# LeoBlinky2018-ENT.net
KiCad netlist of a schematic drawn in Altium Designer
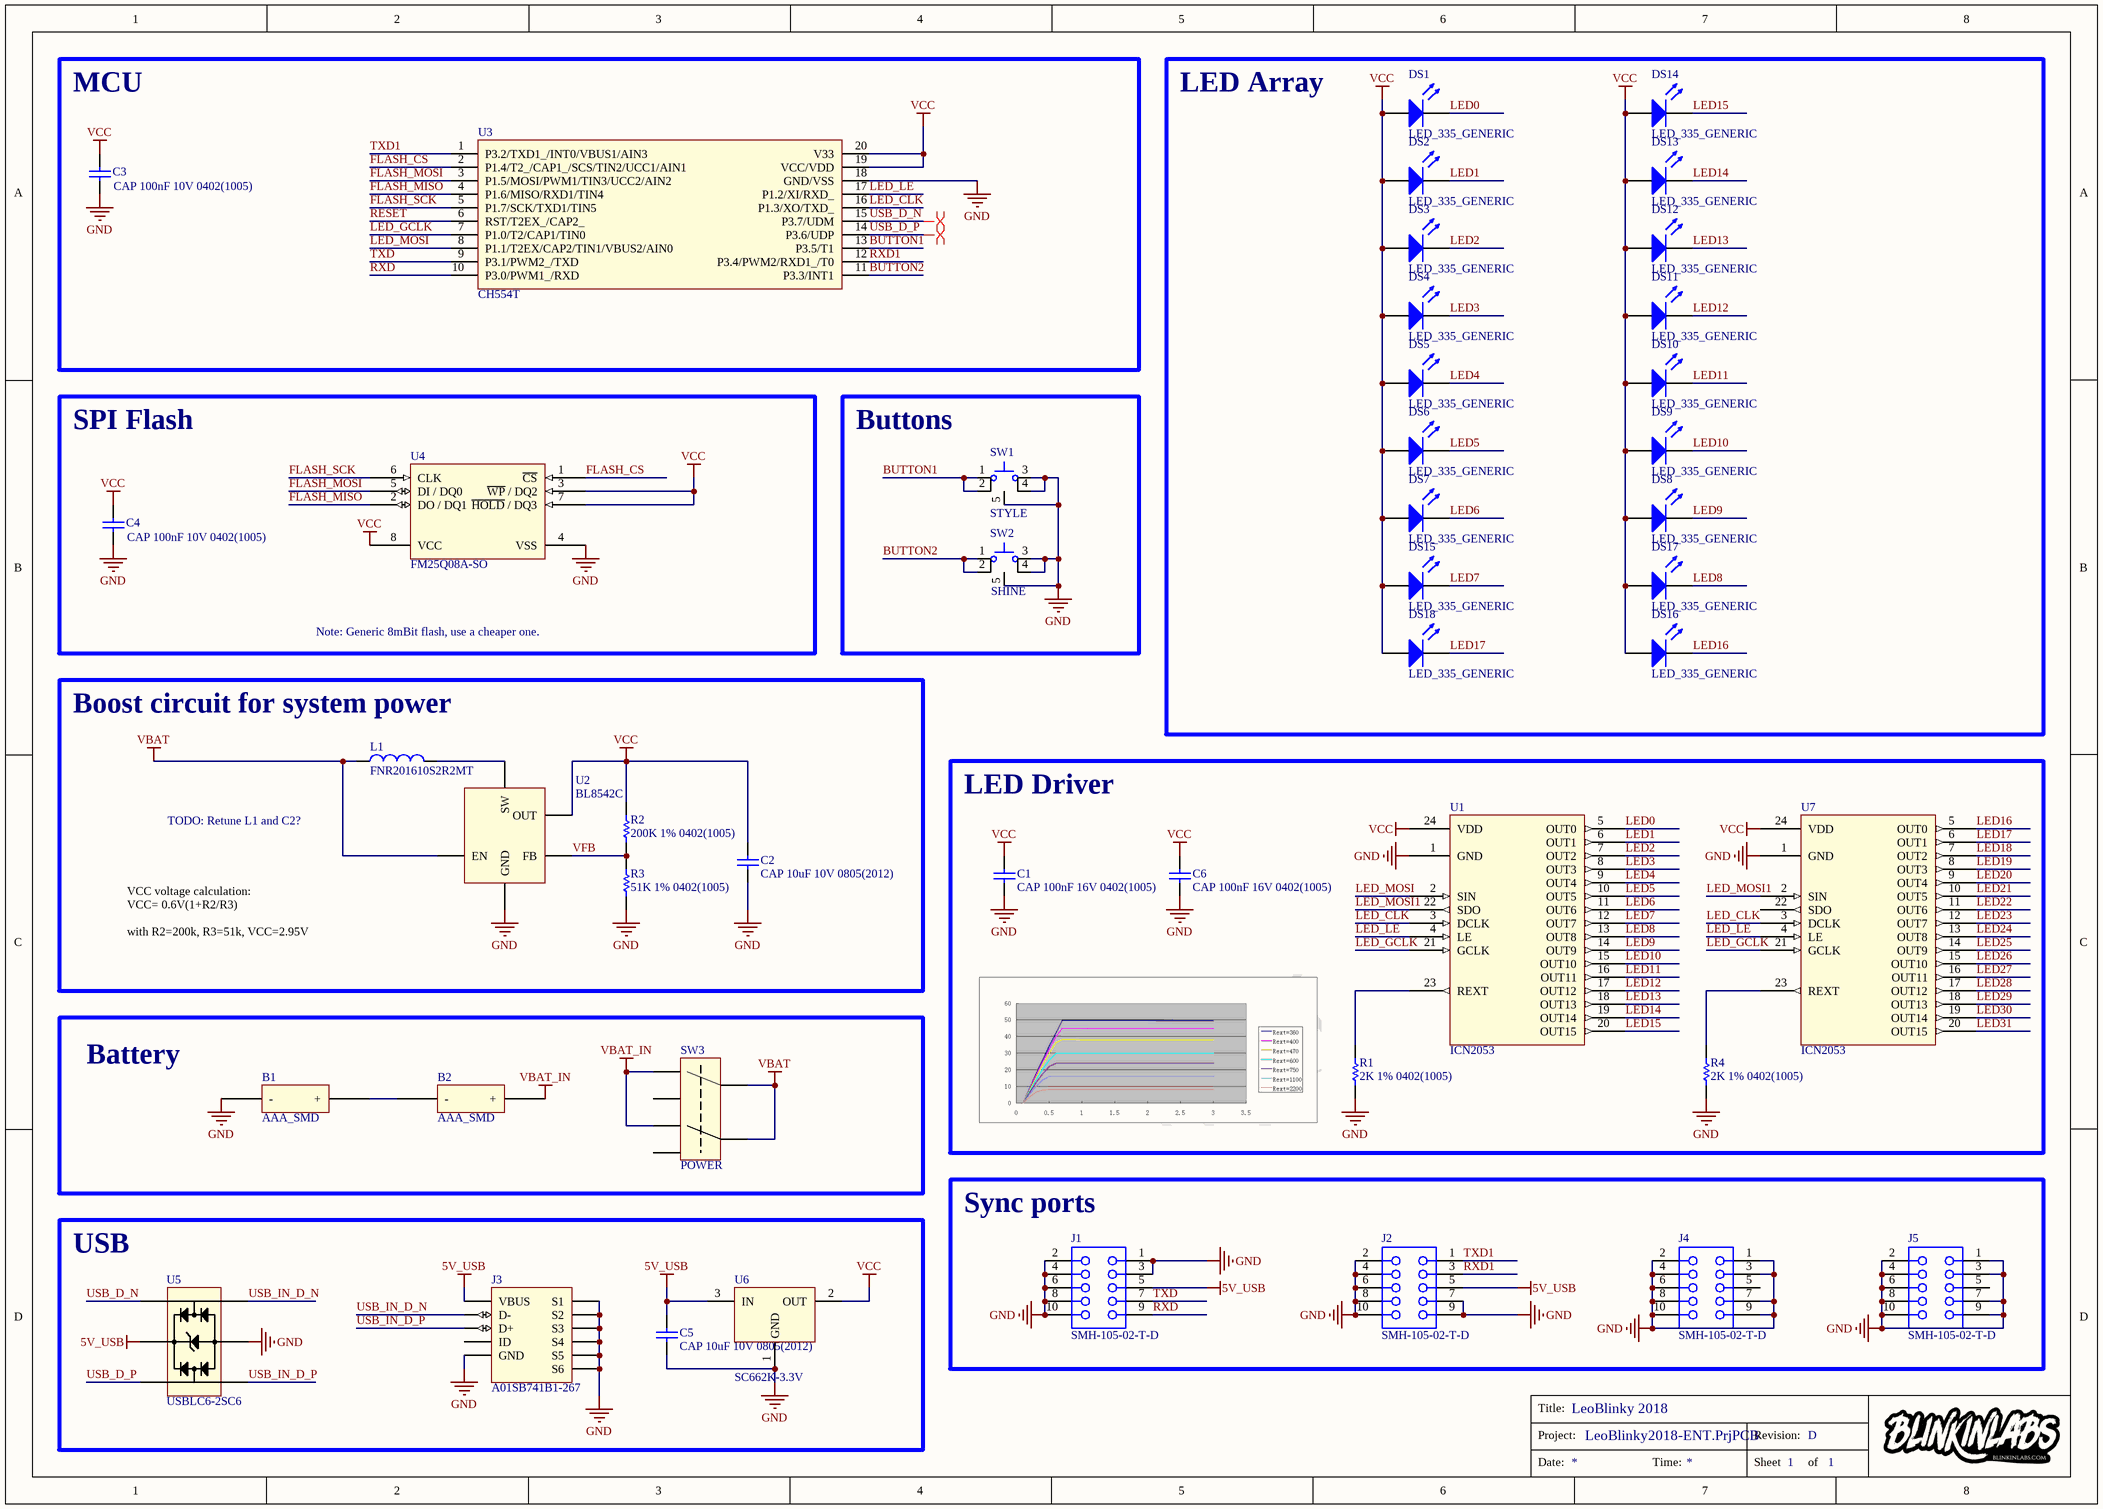
[diagram p0: LeoBlinky2018-ENT.SchDoc]

(export (version "E")
  (design (tool "Eeschema 10.0.6"))
  (components
    (comp (ref "B1")
      (value "AAA_SMD")
      (footprint "AAA_SMD")
      (description "AAA battery holder, surface mount.")
      (libsource (lib "Blinkinlabs") (part "AAA_SMD"))
    )
    (comp (ref "B2")
      (value "AAA_SMD")
      (footprint "AAA_SMD")
      (description "AAA battery holder, surface mount.")
      (libsource (lib "Blinkinlabs") (part "AAA_SMD"))
    )
    (comp (ref "C1")
      (value "CAP 100nF 16V 0402(1005)")
      (footprint "CAPC0402(1005)60_N")
      (description "CAP 100nF 16V -20% to +80% 0402 (1005 Metric) Thickness 0.6mm SMD")
      (fields (field (name "TOLERANCE") "-20% to +80%"))
      (libsource (lib "Altium Content Vault") (part "CAP"))
    )
    (comp (ref "C2")
      (value "CAP 10uF 10V 0805(2012)")
      (footprint "CAPC0805(2012)145_N")
      (description "CAP 10uF 10V ±10% 0805 (2012 Metric) Thickness 1.45mm SMD")
      (fields (field (name "TOLERANCE") "Â±10%"))
      (libsource (lib "Altium Content Vault") (part "CMP-1036-04922-1"))
    )
    (comp (ref "C3")
      (value "CAP 100nF 10V 0402(1005)")
      (footprint "CAPC0402(1005)60_L")
      (description "CAP 100nF 10V ±10% 0402 (1005 Metric) Thickness 0.6mm SMD")
      (fields (field (name "TOLERANCE") "Â±10%"))
      (libsource (lib "Altium Content Vault") (part "CMP-1034-02065-1"))
    )
    (comp (ref "C4")
      (value "CAP 100nF 10V 0402(1005)")
      (footprint "CAPC0402(1005)60_L")
      (description "CAP 100nF 10V ±10% 0402 (1005 Metric) Thickness 0.6mm SMD")
      (fields (field (name "TOLERANCE") "Â±10%"))
      (libsource (lib "Altium Content Vault") (part "CMP-1034-02065-1"))
    )
    (comp (ref "C5")
      (value "CAP 10uF 10V 0805(2012)")
      (footprint "CAPC0805(2012)145_N")
      (description "CAP 10uF 10V ±10% 0805 (2012 Metric) Thickness 1.45mm SMD")
      (fields (field (name "TOLERANCE") "Â±10%"))
      (libsource (lib "Altium Content Vault") (part "CAP"))
    )
    (comp (ref "C6")
      (value "CAP 100nF 16V 0402(1005)")
      (footprint "CAPC0402(1005)60_N")
      (description "CAP 100nF 16V -20% to +80% 0402 (1005 Metric) Thickness 0.6mm SMD")
      (fields (field (name "TOLERANCE") "-20% to +80%"))
      (libsource (lib "Altium Content Vault") (part "CAP"))
    )
    (comp (ref "DS1")
      (value "LED_335_GENERIC")
      (footprint "LED_335_GENERIC")
      (description "SMD LED, side visible, generic")
      (libsource (lib "Blinkinlabs") (part "LED_335_GENERIC"))
    )
    (comp (ref "DS2")
      (value "LED_335_GENERIC")
      (footprint "LED_335_GENERIC")
      (description "SMD LED, side visible, generic")
      (libsource (lib "Blinkinlabs") (part "LED_335_GENERIC"))
    )
    (comp (ref "DS3")
      (value "LED_335_GENERIC")
      (footprint "LED_335_GENERIC")
      (description "SMD LED, side visible, generic")
      (libsource (lib "Blinkinlabs") (part "LED_335_GENERIC"))
    )
    (comp (ref "DS4")
      (value "LED_335_GENERIC")
      (footprint "LED_335_GENERIC")
      (description "SMD LED, side visible, generic")
      (libsource (lib "Blinkinlabs") (part "LED_335_GENERIC"))
    )
    (comp (ref "DS5")
      (value "LED_335_GENERIC")
      (footprint "LED_335_GENERIC")
      (description "SMD LED, side visible, generic")
      (libsource (lib "Blinkinlabs") (part "LED_335_GENERIC"))
    )
    (comp (ref "DS6")
      (value "LED_335_GENERIC")
      (footprint "LED_335_GENERIC")
      (description "SMD LED, side visible, generic")
      (libsource (lib "Blinkinlabs") (part "LED_335_GENERIC"))
    )
    (comp (ref "DS7")
      (value "LED_335_GENERIC")
      (footprint "LED_335_GENERIC")
      (description "SMD LED, side visible, generic")
      (libsource (lib "Blinkinlabs") (part "LED_335_GENERIC"))
    )
    (comp (ref "DS8")
      (value "LED_335_GENERIC")
      (footprint "LED_335_GENERIC")
      (description "SMD LED, side visible, generic")
      (libsource (lib "Blinkinlabs") (part "LED_335_GENERIC"))
    )
    (comp (ref "DS9")
      (value "LED_335_GENERIC")
      (footprint "LED_335_GENERIC")
      (description "SMD LED, side visible, generic")
      (libsource (lib "Blinkinlabs") (part "LED_335_GENERIC"))
    )
    (comp (ref "DS10")
      (value "LED_335_GENERIC")
      (footprint "LED_335_GENERIC")
      (description "SMD LED, side visible, generic")
      (libsource (lib "Blinkinlabs") (part "LED_335_GENERIC"))
    )
    (comp (ref "DS11")
      (value "LED_335_GENERIC")
      (footprint "LED_335_GENERIC")
      (description "SMD LED, side visible, generic")
      (libsource (lib "Blinkinlabs") (part "LED_335_GENERIC"))
    )
    (comp (ref "DS12")
      (value "LED_335_GENERIC")
      (footprint "LED_335_GENERIC")
      (description "SMD LED, side visible, generic")
      (libsource (lib "Blinkinlabs") (part "LED_335_GENERIC"))
    )
    (comp (ref "DS13")
      (value "LED_335_GENERIC")
      (footprint "LED_335_GENERIC")
      (description "SMD LED, side visible, generic")
      (libsource (lib "Blinkinlabs") (part "LED_335_GENERIC"))
    )
    (comp (ref "DS14")
      (value "LED_335_GENERIC")
      (footprint "LED_335_GENERIC")
      (description "SMD LED, side visible, generic")
      (libsource (lib "Blinkinlabs") (part "LED_335_GENERIC"))
    )
    (comp (ref "DS15")
      (value "LED_335_GENERIC")
      (footprint "LED_335_GENERIC")
      (description "SMD LED, side visible, generic")
      (libsource (lib "Blinkinlabs") (part "LED_335_GENERIC"))
    )
    (comp (ref "DS16")
      (value "LED_335_GENERIC")
      (footprint "LED_335_GENERIC")
      (description "SMD LED, side visible, generic")
      (libsource (lib "Blinkinlabs") (part "LED_335_GENERIC"))
    )
    (comp (ref "DS17")
      (value "LED_335_GENERIC")
      (footprint "LED_335_GENERIC")
      (description "SMD LED, side visible, generic")
      (libsource (lib "Blinkinlabs") (part "LED_335_GENERIC"))
    )
    (comp (ref "DS18")
      (value "LED_335_GENERIC")
      (footprint "LED_335_GENERIC")
      (description "SMD LED, side visible, generic")
      (libsource (lib "Blinkinlabs") (part "LED_335_GENERIC"))
    )
    (comp (ref "J1")
      (value "SMH-105-02-T-D")
      (footprint "SMTC-SMH-105-02-X-D")
      (description "SMT Horizontal Socket, -55 to 105 degC, 2.54 mm Pitch, 10-Pin, Female, RoHS")
      (fields (field (name "MANUFACTURER") "Samtec"))
      (libsource (lib "Altium Content Vault") (part "SMTC-SMH-105-02-X-D-X"))
    )
    (comp (ref "J2")
      (value "SMH-105-02-T-D")
      (footprint "SMTC-SMH-105-02-X-D")
      (description "SMT Horizontal Socket, -55 to 105 degC, 2.54 mm Pitch, 10-Pin, Female, RoHS")
      (fields (field (name "MANUFACTURER") "Samtec"))
      (libsource (lib "Altium Content Vault") (part "SMTC-SMH-105-02-X-D-X"))
    )
    (comp (ref "J3")
      (value "A01SB741B1-267")
      (footprint "A01SB741B1-267")
      (description "Micro USB B type 四脚全插牛角")
      (libsource (lib "Blinkinlabs") (part "A01SB741B1-267"))
    )
    (comp (ref "J4")
      (value "SMH-105-02-T-D")
      (footprint "SMTC-SMH-105-02-X-D")
      (description "SMT Horizontal Socket, -55 to 105 degC, 2.54 mm Pitch, 10-Pin, Female, RoHS")
      (fields (field (name "MANUFACTURER") "Samtec"))
      (libsource (lib "Altium Content Vault") (part "SMTC-SMH-105-02-X-D-X"))
    )
    (comp (ref "J5")
      (value "SMH-105-02-T-D")
      (footprint "SMTC-SMH-105-02-X-D")
      (description "SMT Horizontal Socket, -55 to 105 degC, 2.54 mm Pitch, 10-Pin, Female, RoHS")
      (fields (field (name "MANUFACTURER") "Samtec"))
      (libsource (lib "Altium Content Vault") (part "SMTC-SMH-105-02-X-D-X"))
    )
    (comp (ref "L1")
      (value "FNR201610S2R2MT")
      (footprint "FNR201610S")
      (description "Wire Wound SMD Power Inductors 2.0×1.6×1.0 2.2uH")
      (libsource (lib "Blinkinlabs") (part "FNR201610S2R2MT"))
    )
    (comp (ref "R1")
      (value "2K 1% 0402(1005)")
      (footprint "RESC0402(1005)_N")
      (description "2K 0.063W 1% 0402 (1005 Metric)  SMD")
      (fields (field (name "POWER") "0.063 W") (field (name "TOLERANCE") "1 %"))
      (libsource (lib "Altium Content Vault") (part "RES"))
    )
    (comp (ref "R2")
      (value "200K 1% 0402(1005)")
      (footprint "RESC0402(1005)_L")
      (description "200K 0.063W 1% 0402 (1005 Metric)  SMD")
      (fields (field (name "TOLERANCE") "1 %") (field (name "POWER") "0.063 W"))
      (libsource (lib "Altium Content Vault") (part "RES"))
    )
    (comp (ref "R3")
      (value "51K 1% 0402(1005)")
      (footprint "RESC0402(1005)_L")
      (description "51K 0.063W 1% 0402 (1005 Metric)  SMD")
      (fields (field (name "TOLERANCE") "1 %") (field (name "POWER") "0.063 W"))
      (libsource (lib "Altium Content Vault") (part "RES"))
    )
    (comp (ref "R4")
      (value "2K 1% 0402(1005)")
      (footprint "RESC0402(1005)_N")
      (description "2K 0.063W 1% 0402 (1005 Metric)  SMD")
      (fields (field (name "POWER") "0.063 W") (field (name "TOLERANCE") "1 %"))
      (libsource (lib "Altium Content Vault") (part "RES"))
    )
    (comp (ref "SW1")
      (value "STYLE")
      (footprint "TD-07XB")
      (description "Tact Switch")
      (fields
        (field (name "MANUFACTURER") "ShenZhen XieJia Electronics Co Ltd")
        (field (name "PARTNUMBER") "TD-07XB")
      )
      (libsource (lib "Blinkinlabs") (part "TD-07XB"))
    )
    (comp (ref "SW2")
      (value "SHINE")
      (footprint "TD-07XB")
      (description "Tact Switch")
      (fields
        (field (name "MANUFACTURER") "ShenZhen XieJia Electronics Co Ltd")
        (field (name "PARTNUMBER") "TD-07XB")
      )
      (libsource (lib "Blinkinlabs") (part "TD-07XB"))
    )
    (comp (ref "SW3")
      (value "POWER")
      (footprint "MSK-1133-NOHOLE")
      (description "SMD micro toggle switch, 2 position, 2 circuit")
      (libsource (lib "Blinkinlabs") (part "MSK-1133"))
    )
    (comp (ref "U1")
      (value "ICN2053")
      (footprint "SOP64P600X175-24N")
      (description "16-Channel PWM Constant Current LED Sink Driver")
      (fields (field (name "MANUFACTURER") "ChipOne"))
      (libsource (lib "Blinkinlabs") (part "ICN2053"))
    )
    (comp (ref "U2")
      (value "BL8542C")
      (footprint "SOT95P280X130-5N")
      (description "0.85V startup, 1MHz, 300mA Iout,  Synchronous Boost Converter (adjustable output)")
      (fields (field (name "MANUFACTURER") "Belling"))
      (libsource (lib "Blinkinlabs") (part "BL8542C"))
    )
    (comp (ref "U3")
      (value "CH554T")
      (footprint "TSOP65P660X110-20N")
      (description "8-bit enhanced USB microcontroller")
      (fields (field (name "MANUFACTURER") "WCH"))
      (libsource (lib "Blinkinlabs") (part "CH554T"))
    )
    (comp (ref "U4")
      (value "FM25Q08A-SO")
      (footprint "SOP127P600X175-8N")
      (description "8M-BIT SERIAL FLASH MEMORY, 150mil width")
      (fields (field (name "MANUFACTURER") "Shanghai Fudan Microelectronics Group Company Limited"))
      (libsource (lib "Blinkinlabs") (part "FM25Q08A-SO"))
    )
    (comp (ref "U5")
      (value "USBLC6-2SC6")
      (footprint "SOT95P280X145-6N")
      (description "Very low capacitance ESD protection")
      (fields (field (name "MANUFACTURER") "STMicroelectronics"))
      (libsource (lib "Blinkinlabs") (part "USBLC6-2SC6"))
    )
    (comp (ref "U6")
      (value "SC662K-3.3V")
      (footprint "SOT95P230X117-3N")
      (description "3.3V, 250mA Low dropout voltage regulator IC")
      (libsource (lib "Blinkinlabs") (part "SC662K-3.3V"))
    )
    (comp (ref "U7")
      (value "ICN2053")
      (footprint "SOP64P600X175-24N")
      (description "16-Channel PWM Constant Current LED Sink Driver")
      (fields (field (name "MANUFACTURER") "ChipOne"))
      (libsource (lib "Blinkinlabs") (part "ICN2053"))
    )
  )
  (nets
    (net (code "1") (name "/BUTTON1") (class "Default")
      (node (ref "SW1") (pin "1") (pinfunction "1_1") (pintype "passive"))
      (node (ref "SW1") (pin "2") (pinfunction "2_2") (pintype "passive"))
      (node (ref "U3") (pin "13") (pinfunction "P3.5/T1_13") (pintype "passive"))
    )
    (net (code "2") (name "/BUTTON2") (class "Default")
      (node (ref "SW2") (pin "1") (pinfunction "1_1") (pintype "passive"))
      (node (ref "SW2") (pin "2") (pinfunction "2_2") (pintype "passive"))
      (node (ref "U3") (pin "11") (pinfunction "P3.3/INT1_11") (pintype "passive"))
    )
    (net (code "3") (name "/FLASH_CS") (class "Default")
      (node (ref "U3") (pin "2") (pinfunction "P1.4/T2_/CAP1_/SCS/TIN2/UCC1/AIN1_2") (pintype "passive"))
      (node (ref "U4") (pin "1") (pinfunction "~{CS}_1") (pintype "input"))
    )
    (net (code "4") (name "/FLASH_MISO") (class "Default")
      (node (ref "U3") (pin "4") (pinfunction "P1.6/MISO/RXD1/TIN4_4") (pintype "passive"))
      (node (ref "U4") (pin "2") (pinfunction "DO_/_DQ1_2") (pintype "bidirectional"))
    )
    (net (code "5") (name "/FLASH_MOSI") (class "Default")
      (node (ref "U3") (pin "3") (pinfunction "P1.5/MOSI/PWM1/TIN3/UCC2/AIN2_3") (pintype "passive"))
      (node (ref "U4") (pin "5") (pinfunction "DI_/_DQ0_5") (pintype "bidirectional"))
    )
    (net (code "6") (name "/FLASH_SCK") (class "Default")
      (node (ref "U3") (pin "5") (pinfunction "P1.7/SCK/TXD1/TIN5_5") (pintype "passive"))
      (node (ref "U4") (pin "6") (pinfunction "CLK_6") (pintype "input"))
    )
    (net (code "7") (name "/LED0") (class "Default")
      (node (ref "DS1") (pin "1") (pinfunction "1_1") (pintype "passive"))
      (node (ref "U1") (pin "5") (pinfunction "OUT0_5") (pintype "output"))
    )
    (net (code "8") (name "/LED1") (class "Default")
      (node (ref "DS2") (pin "1") (pinfunction "1_1") (pintype "passive"))
      (node (ref "U1") (pin "6") (pinfunction "OUT1_6") (pintype "output"))
    )
    (net (code "9") (name "/LED2") (class "Default")
      (node (ref "DS3") (pin "1") (pinfunction "1_1") (pintype "passive"))
      (node (ref "U1") (pin "7") (pinfunction "OUT2_7") (pintype "output"))
    )
    (net (code "10") (name "/LED3") (class "Default")
      (node (ref "DS4") (pin "1") (pinfunction "1_1") (pintype "passive"))
      (node (ref "U1") (pin "8") (pinfunction "OUT3_8") (pintype "output"))
    )
    (net (code "11") (name "/LED4") (class "Default")
      (node (ref "DS5") (pin "1") (pinfunction "1_1") (pintype "passive"))
      (node (ref "U1") (pin "9") (pinfunction "OUT4_9") (pintype "output"))
    )
    (net (code "12") (name "/LED5") (class "Default")
      (node (ref "DS6") (pin "1") (pinfunction "1_1") (pintype "passive"))
      (node (ref "U1") (pin "10") (pinfunction "OUT5_10") (pintype "output"))
    )
    (net (code "13") (name "/LED6") (class "Default")
      (node (ref "DS7") (pin "1") (pinfunction "1_1") (pintype "passive"))
      (node (ref "U1") (pin "11") (pinfunction "OUT6_11") (pintype "output"))
    )
    (net (code "14") (name "/LED7") (class "Default")
      (node (ref "DS15") (pin "1") (pinfunction "1_1") (pintype "passive"))
      (node (ref "U1") (pin "12") (pinfunction "OUT7_12") (pintype "output"))
    )
    (net (code "15") (name "/LED8") (class "Default")
      (node (ref "DS17") (pin "1") (pinfunction "1_1") (pintype "passive"))
      (node (ref "U1") (pin "13") (pinfunction "OUT8_13") (pintype "output"))
    )
    (net (code "16") (name "/LED9") (class "Default")
      (node (ref "DS8") (pin "1") (pinfunction "1_1") (pintype "passive"))
      (node (ref "U1") (pin "14") (pinfunction "OUT9_14") (pintype "output"))
    )
    (net (code "17") (name "/LED10") (class "Default")
      (node (ref "DS9") (pin "1") (pinfunction "1_1") (pintype "passive"))
      (node (ref "U1") (pin "15") (pinfunction "OUT10_15") (pintype "output"))
    )
    (net (code "18") (name "/LED11") (class "Default")
      (node (ref "DS10") (pin "1") (pinfunction "1_1") (pintype "passive"))
      (node (ref "U1") (pin "16") (pinfunction "OUT11_16") (pintype "output"))
    )
    (net (code "19") (name "/LED12") (class "Default")
      (node (ref "DS11") (pin "1") (pinfunction "1_1") (pintype "passive"))
      (node (ref "U1") (pin "17") (pinfunction "OUT12_17") (pintype "output"))
    )
    (net (code "20") (name "/LED13") (class "Default")
      (node (ref "DS12") (pin "1") (pinfunction "1_1") (pintype "passive"))
      (node (ref "U1") (pin "18") (pinfunction "OUT13_18") (pintype "output"))
    )
    (net (code "21") (name "/LED14") (class "Default")
      (node (ref "DS13") (pin "1") (pinfunction "1_1") (pintype "passive"))
      (node (ref "U1") (pin "19") (pinfunction "OUT14_19") (pintype "output"))
    )
    (net (code "22") (name "/LED15") (class "Default")
      (node (ref "DS14") (pin "1") (pinfunction "1_1") (pintype "passive"))
      (node (ref "U1") (pin "20") (pinfunction "OUT15_20") (pintype "output"))
    )
    (net (code "23") (name "/LED16") (class "Default")
      (node (ref "DS16") (pin "1") (pinfunction "1_1") (pintype "passive"))
      (node (ref "U7") (pin "5") (pinfunction "OUT0_5") (pintype "output"))
    )
    (net (code "24") (name "/LED17") (class "Default")
      (node (ref "DS18") (pin "1") (pinfunction "1_1") (pintype "passive"))
      (node (ref "U7") (pin "6") (pinfunction "OUT1_6") (pintype "output"))
    )
    (net (code "25") (name "/LED18") (class "Default")
      (node (ref "U7") (pin "7") (pinfunction "OUT2_7") (pintype "output"))
    )
    (net (code "26") (name "/LED19") (class "Default")
      (node (ref "U7") (pin "8") (pinfunction "OUT3_8") (pintype "output"))
    )
    (net (code "27") (name "/LED20") (class "Default")
      (node (ref "U7") (pin "9") (pinfunction "OUT4_9") (pintype "output"))
    )
    (net (code "28") (name "/LED21") (class "Default")
      (node (ref "U7") (pin "10") (pinfunction "OUT5_10") (pintype "output"))
    )
    (net (code "29") (name "/LED22") (class "Default")
      (node (ref "U7") (pin "11") (pinfunction "OUT6_11") (pintype "output"))
    )
    (net (code "30") (name "/LED23") (class "Default")
      (node (ref "U7") (pin "12") (pinfunction "OUT7_12") (pintype "output"))
    )
    (net (code "31") (name "/LED24") (class "Default")
      (node (ref "U7") (pin "13") (pinfunction "OUT8_13") (pintype "output"))
    )
    (net (code "32") (name "/LED25") (class "Default")
      (node (ref "U7") (pin "14") (pinfunction "OUT9_14") (pintype "output"))
    )
    (net (code "33") (name "/LED26") (class "Default")
      (node (ref "U7") (pin "15") (pinfunction "OUT10_15") (pintype "output"))
    )
    (net (code "34") (name "/LED27") (class "Default")
      (node (ref "U7") (pin "16") (pinfunction "OUT11_16") (pintype "output"))
    )
    (net (code "35") (name "/LED28") (class "Default")
      (node (ref "U7") (pin "17") (pinfunction "OUT12_17") (pintype "output"))
    )
    (net (code "36") (name "/LED29") (class "Default")
      (node (ref "U7") (pin "18") (pinfunction "OUT13_18") (pintype "output"))
    )
    (net (code "37") (name "/LED30") (class "Default")
      (node (ref "U7") (pin "19") (pinfunction "OUT14_19") (pintype "output"))
    )
    (net (code "38") (name "/LED31") (class "Default")
      (node (ref "U7") (pin "20") (pinfunction "OUT15_20") (pintype "output"))
    )
    (net (code "39") (name "/LED_CLK") (class "Default")
      (node (ref "U1") (pin "3") (pinfunction "DCLK_3") (pintype "input"))
      (node (ref "U3") (pin "16") (pinfunction "P1.3/XO/TXD__16") (pintype "passive"))
      (node (ref "U7") (pin "3") (pinfunction "DCLK_3") (pintype "input"))
    )
    (net (code "40") (name "/LED_GCLK") (class "Default")
      (node (ref "U1") (pin "21") (pinfunction "GCLK_21") (pintype "input"))
      (node (ref "U3") (pin "7") (pinfunction "P1.0/T2/CAP1/TIN0_7") (pintype "passive"))
      (node (ref "U7") (pin "21") (pinfunction "GCLK_21") (pintype "input"))
    )
    (net (code "41") (name "/LED_LE") (class "Default")
      (node (ref "U1") (pin "4") (pinfunction "LE_4") (pintype "input"))
      (node (ref "U3") (pin "17") (pinfunction "P1.2/XI/RXD__17") (pintype "passive"))
      (node (ref "U7") (pin "4") (pinfunction "LE_4") (pintype "input"))
    )
    (net (code "42") (name "/LED_MOSI") (class "Default")
      (node (ref "U1") (pin "2") (pinfunction "SIN_2") (pintype "input"))
      (node (ref "U3") (pin "8") (pinfunction "P1.1/T2EX/CAP2/TIN1/VBUS2/AIN0_8") (pintype "passive"))
    )
    (net (code "43") (name "/LED_MOSI1") (class "Default")
      (node (ref "U1") (pin "22") (pinfunction "SDO_22") (pintype "output"))
      (node (ref "U7") (pin "2") (pinfunction "SIN_2") (pintype "input"))
    )
    (net (code "44") (name "/RESET") (class "Default")
      (node (ref "U3") (pin "6") (pinfunction "RST/T2EX_/CAP2__6") (pintype "passive"))
    )
    (net (code "45") (name "/RXD") (class "Default")
      (node (ref "J1") (pin "9") (pinfunction "9_9") (pintype "passive"))
      (node (ref "U3") (pin "10") (pinfunction "P3.0/PWM1_/RXD_10") (pintype "passive"))
    )
    (net (code "46") (name "/RXD1") (class "Default")
      (node (ref "J2") (pin "3") (pinfunction "3_3") (pintype "passive"))
      (node (ref "U3") (pin "12") (pinfunction "P3.4/PWM2/RXD1_/T0_12") (pintype "passive"))
    )
    (net (code "47") (name "/TXD") (class "Default")
      (node (ref "J1") (pin "7") (pinfunction "7_7") (pintype "passive"))
      (node (ref "U3") (pin "9") (pinfunction "P3.1/PWM2_/TXD_9") (pintype "passive"))
    )
    (net (code "48") (name "/TXD1") (class "Default")
      (node (ref "J2") (pin "1") (pinfunction "1_1") (pintype "passive"))
      (node (ref "U3") (pin "1") (pinfunction "P3.2/TXD1_/INT0/VBUS1/AIN3_1") (pintype "passive"))
    )
    (net (code "49") (name "/USB_D_N") (class "Default")
      (node (ref "U3") (pin "15") (pinfunction "P3.7/UDM_15") (pintype "passive"))
      (node (ref "U5") (pin "4") (pinfunction "I/O2_4") (pintype "passive"))
    )
    (net (code "50") (name "/USB_D_P") (class "Default")
      (node (ref "U3") (pin "14") (pinfunction "P3.6/UDP_14") (pintype "passive"))
      (node (ref "U5") (pin "6") (pinfunction "I/O1_6") (pintype "passive"))
    )
    (net (code "51") (name "/USB_IN_D_N") (class "Default")
      (node (ref "J3") (pin "D-") (pinfunction "D-_D-") (pintype "bidirectional"))
      (node (ref "U5") (pin "3") (pinfunction "I/O2_3") (pintype "passive"))
    )
    (net (code "52") (name "/USB_IN_D_P") (class "Default")
      (node (ref "J3") (pin "D+") (pinfunction "D+_D+") (pintype "bidirectional"))
      (node (ref "U5") (pin "1") (pinfunction "I/O1_1") (pintype "passive"))
    )
    (net (code "53") (name "/VFB") (class "Default")
      (node (ref "R2") (pin "1") (pinfunction "1_1") (pintype "passive"))
      (node (ref "R3") (pin "2") (pinfunction "2_2") (pintype "passive"))
      (node (ref "U2") (pin "1") (pinfunction "FB_1") (pintype "passive"))
    )
    (net (code "54") (name "5V_USB") (class "Default")
      (node (ref "C5") (pin "2") (pinfunction "2_2") (pintype "passive"))
      (node (ref "J1") (pin "5") (pinfunction "5_5") (pintype "passive"))
      (node (ref "J2") (pin "5") (pinfunction "5_5") (pintype "passive"))
      (node (ref "J3") (pin "VBUS") (pinfunction "VBUS_VBUS") (pintype "power_in"))
      (node (ref "U5") (pin "5") (pinfunction "5_5") (pintype "passive"))
      (node (ref "U6") (pin "3") (pinfunction "IN_3") (pintype "power_in"))
    )
    (net (code "55") (name "GND") (class "Default")
      (node (ref "B1") (pin "2") (pinfunction "-_2") (pintype "power_in"))
      (node (ref "C1") (pin "1") (pinfunction "1_1") (pintype "passive"))
      (node (ref "C2") (pin "1") (pinfunction "1_1") (pintype "passive"))
      (node (ref "C3") (pin "1") (pinfunction "1_1") (pintype "passive"))
      (node (ref "C4") (pin "1") (pinfunction "1_1") (pintype "passive"))
      (node (ref "C5") (pin "1") (pinfunction "1_1") (pintype "passive"))
      (node (ref "C6") (pin "1") (pinfunction "1_1") (pintype "passive"))
      (node (ref "J1") (pin "1") (pinfunction "1_1") (pintype "passive"))
      (node (ref "J1") (pin "10") (pinfunction "10_10") (pintype "passive"))
      (node (ref "J1") (pin "2") (pinfunction "2_2") (pintype "passive"))
      (node (ref "J1") (pin "3") (pinfunction "3_3") (pintype "passive"))
      (node (ref "J1") (pin "4") (pinfunction "4_4") (pintype "passive"))
      (node (ref "J1") (pin "6") (pinfunction "6_6") (pintype "passive"))
      (node (ref "J1") (pin "8") (pinfunction "8_8") (pintype "passive"))
      (node (ref "J2") (pin "10") (pinfunction "10_10") (pintype "passive"))
      (node (ref "J2") (pin "2") (pinfunction "2_2") (pintype "passive"))
      (node (ref "J2") (pin "4") (pinfunction "4_4") (pintype "passive"))
      (node (ref "J2") (pin "6") (pinfunction "6_6") (pintype "passive"))
      (node (ref "J2") (pin "7") (pinfunction "7_7") (pintype "passive"))
      (node (ref "J2") (pin "8") (pinfunction "8_8") (pintype "passive"))
      (node (ref "J2") (pin "9") (pinfunction "9_9") (pintype "passive"))
      (node (ref "J3") (pin "GND") (pinfunction "GND_GND") (pintype "power_in"))
      (node (ref "J3") (pin "S1") (pinfunction "S1_S1") (pintype "passive"))
      (node (ref "J3") (pin "S2") (pinfunction "S2_S2") (pintype "passive"))
      (node (ref "J3") (pin "S3") (pinfunction "S3_S3") (pintype "passive"))
      (node (ref "J3") (pin "S4") (pinfunction "S4_S4") (pintype "passive"))
      (node (ref "J3") (pin "S5") (pinfunction "S5_S5") (pintype "passive"))
      (node (ref "J3") (pin "S6") (pinfunction "S6_S6") (pintype "passive"))
      (node (ref "J4") (pin "1") (pinfunction "1_1") (pintype "passive"))
      (node (ref "J4") (pin "10") (pinfunction "10_10") (pintype "passive"))
      (node (ref "J4") (pin "2") (pinfunction "2_2") (pintype "passive"))
      (node (ref "J4") (pin "3") (pinfunction "3_3") (pintype "passive"))
      (node (ref "J4") (pin "4") (pinfunction "4_4") (pintype "passive"))
      (node (ref "J4") (pin "6") (pinfunction "6_6") (pintype "passive"))
      (node (ref "J4") (pin "7") (pinfunction "7_7") (pintype "passive"))
      (node (ref "J4") (pin "8") (pinfunction "8_8") (pintype "passive"))
      (node (ref "J4") (pin "9") (pinfunction "9_9") (pintype "passive"))
      (node (ref "J5") (pin "1") (pinfunction "1_1") (pintype "passive"))
      (node (ref "J5") (pin "10") (pinfunction "10_10") (pintype "passive"))
      (node (ref "J5") (pin "2") (pinfunction "2_2") (pintype "passive"))
      (node (ref "J5") (pin "3") (pinfunction "3_3") (pintype "passive"))
      (node (ref "J5") (pin "4") (pinfunction "4_4") (pintype "passive"))
      (node (ref "J5") (pin "6") (pinfunction "6_6") (pintype "passive"))
      (node (ref "J5") (pin "7") (pinfunction "7_7") (pintype "passive"))
      (node (ref "J5") (pin "8") (pinfunction "8_8") (pintype "passive"))
      (node (ref "J5") (pin "9") (pinfunction "9_9") (pintype "passive"))
      (node (ref "R1") (pin "1") (pinfunction "1_1") (pintype "passive"))
      (node (ref "R3") (pin "1") (pinfunction "1_1") (pintype "passive"))
      (node (ref "R4") (pin "1") (pinfunction "1_1") (pintype "passive"))
      (node (ref "SW1") (pin "3") (pinfunction "3_3") (pintype "passive"))
      (node (ref "SW1") (pin "4") (pinfunction "4_4") (pintype "passive"))
      (node (ref "SW1") (pin "5") (pinfunction "5_5") (pintype "passive"))
      (node (ref "SW2") (pin "3") (pinfunction "3_3") (pintype "passive"))
      (node (ref "SW2") (pin "4") (pinfunction "4_4") (pintype "passive"))
      (node (ref "SW2") (pin "5") (pinfunction "5_5") (pintype "passive"))
      (node (ref "U1") (pin "1") (pinfunction "GND_1") (pintype "power_in"))
      (node (ref "U2") (pin "2") (pinfunction "GND_2") (pintype "passive"))
      (node (ref "U3") (pin "18") (pinfunction "GND/VSS_18") (pintype "power_in"))
      (node (ref "U4") (pin "4") (pinfunction "VSS_4") (pintype "power_in"))
      (node (ref "U5") (pin "2") (pinfunction "GND_2") (pintype "passive"))
      (node (ref "U6") (pin "1") (pinfunction "GND_1") (pintype "power_in"))
      (node (ref "U7") (pin "1") (pinfunction "GND_1") (pintype "power_in"))
    )
    (net (code "56") (name "Net-(B1-+)") (class "Default")
      (node (ref "B1") (pin "1") (pinfunction "+_1") (pintype "power_in"))
      (node (ref "B2") (pin "2") (pinfunction "-_2") (pintype "power_in"))
    )
    (net (code "57") (name "Net-(U1-REXT)") (class "Default")
      (node (ref "R1") (pin "2") (pinfunction "2_2") (pintype "passive"))
      (node (ref "U1") (pin "23") (pinfunction "REXT_23") (pintype "output"))
    )
    (net (code "58") (name "Net-(U2-SW)") (class "Default")
      (node (ref "L1") (pin "2") (pinfunction "2_2") (pintype "passive"))
      (node (ref "U2") (pin "4") (pinfunction "SW_4") (pintype "passive"))
    )
    (net (code "59") (name "Net-(U7-REXT)") (class "Default")
      (node (ref "R4") (pin "2") (pinfunction "2_2") (pintype "passive"))
      (node (ref "U7") (pin "23") (pinfunction "REXT_23") (pintype "output"))
    )
    (net (code "60") (name "VBAT") (class "Default")
      (node (ref "L1") (pin "1") (pinfunction "1_1") (pintype "passive"))
      (node (ref "SW3") (pin "2") (pintype "passive"))
      (node (ref "SW3") (pin "5") (pintype "passive"))
      (node (ref "U2") (pin "3") (pinfunction "EN_3") (pintype "passive"))
    )
    (net (code "61") (name "VBAT_IN") (class "Default")
      (node (ref "B2") (pin "1") (pinfunction "+_1") (pintype "power_in"))
      (node (ref "SW3") (pin "1") (pinfunction "A_1") (pintype "passive"))
      (node (ref "SW3") (pin "6") (pintype "passive"))
    )
    (net (code "62") (name "VCC") (class "Default")
      (node (ref "C1") (pin "2") (pinfunction "2_2") (pintype "passive"))
      (node (ref "C2") (pin "2") (pinfunction "2_2") (pintype "passive"))
      (node (ref "C3") (pin "2") (pinfunction "2_2") (pintype "passive"))
      (node (ref "C4") (pin "2") (pinfunction "2_2") (pintype "passive"))
      (node (ref "C6") (pin "2") (pinfunction "2_2") (pintype "passive"))
      (node (ref "DS1") (pin "2") (pinfunction "1_2") (pintype "passive"))
      (node (ref "DS10") (pin "2") (pinfunction "1_2") (pintype "passive"))
      (node (ref "DS11") (pin "2") (pinfunction "1_2") (pintype "passive"))
      (node (ref "DS12") (pin "2") (pinfunction "1_2") (pintype "passive"))
      (node (ref "DS13") (pin "2") (pinfunction "1_2") (pintype "passive"))
      (node (ref "DS14") (pin "2") (pinfunction "1_2") (pintype "passive"))
      (node (ref "DS15") (pin "2") (pinfunction "1_2") (pintype "passive"))
      (node (ref "DS16") (pin "2") (pinfunction "1_2") (pintype "passive"))
      (node (ref "DS17") (pin "2") (pinfunction "1_2") (pintype "passive"))
      (node (ref "DS18") (pin "2") (pinfunction "1_2") (pintype "passive"))
      (node (ref "DS2") (pin "2") (pinfunction "1_2") (pintype "passive"))
      (node (ref "DS3") (pin "2") (pinfunction "1_2") (pintype "passive"))
      (node (ref "DS4") (pin "2") (pinfunction "1_2") (pintype "passive"))
      (node (ref "DS5") (pin "2") (pinfunction "1_2") (pintype "passive"))
      (node (ref "DS6") (pin "2") (pinfunction "1_2") (pintype "passive"))
      (node (ref "DS7") (pin "2") (pinfunction "1_2") (pintype "passive"))
      (node (ref "DS8") (pin "2") (pinfunction "1_2") (pintype "passive"))
      (node (ref "DS9") (pin "2") (pinfunction "1_2") (pintype "passive"))
      (node (ref "R2") (pin "2") (pinfunction "2_2") (pintype "passive"))
      (node (ref "U1") (pin "24") (pinfunction "VDD_24") (pintype "power_in"))
      (node (ref "U2") (pin "5") (pinfunction "OUT_5") (pintype "passive"))
      (node (ref "U3") (pin "19") (pinfunction "VCC/VDD_19") (pintype "power_in"))
      (node (ref "U3") (pin "20") (pinfunction "V33_20") (pintype "power_in"))
      (node (ref "U4") (pin "3") (pinfunction "~{WP}_/_DQ2_3") (pintype "input"))
      (node (ref "U4") (pin "7") (pinfunction "~{HOLD}_/_DQ3_7") (pintype "input"))
      (node (ref "U4") (pin "8") (pinfunction "VCC_8") (pintype "power_in"))
      (node (ref "U6") (pin "2") (pinfunction "OUT_2") (pintype "power_in"))
      (node (ref "U7") (pin "24") (pinfunction "VDD_24") (pintype "power_in"))
    )
    (net (code "63") (name "unconnected-(J3-PadID)") (class "Default")
      (node (ref "J3") (pin "ID") (pinfunction "ID_ID") (pintype "passive"))
    )
    (net (code "64") (name "unconnected-(J4-Pad5)") (class "Default")
      (node (ref "J4") (pin "5") (pinfunction "5_5") (pintype "passive"))
    )
    (net (code "65") (name "unconnected-(J5-Pad5)") (class "Default")
      (node (ref "J5") (pin "5") (pinfunction "5_5") (pintype "passive"))
    )
    (net (code "66") (name "unconnected-(SW3-Pad3)") (class "Default")
      (node (ref "SW3") (pin "3") (pintype "passive"))
    )
    (net (code "67") (name "unconnected-(SW3-Pad4)") (class "Default")
      (node (ref "SW3") (pin "4") (pintype "passive"))
    )
    (net (code "68") (name "unconnected-(U7-SDO-Pad22)") (class "Default")
      (node (ref "U7") (pin "22") (pinfunction "SDO_22") (pintype "output"))
    )
  )
)
